# ETHERNET.net
KiCad netlist of a schematic drawn in Altium Designer
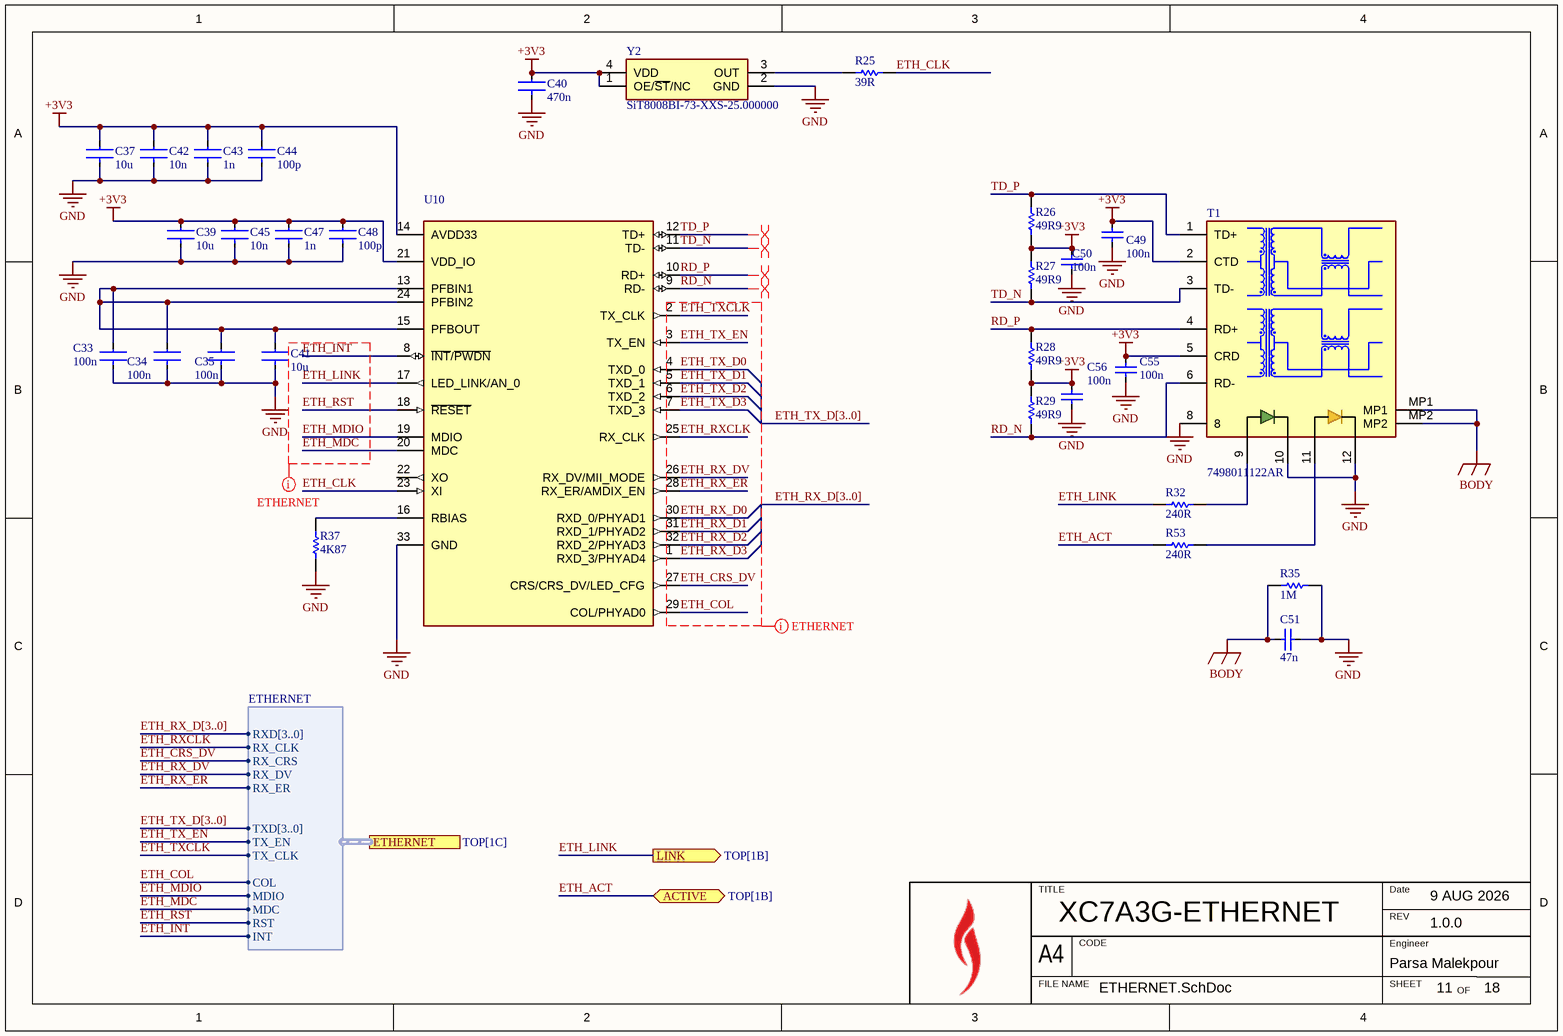
[diagram p0: ETHERNET.SchDoc]

(export (version "E")
  (design (tool "Eeschema 10.0.6"))
  (components
    (comp (ref "C33")
      (value "100n")
      (footprint "FP-C1005-050-0_05-IPC_C")
      (description "Multilayer Ceramic Capacitors 100nF ±10% 50V X7R SMD 0402")
      (fields (field (name "VOLTAGE") "50V") (field (name "TOLERANCE") "10%"))
      (libsource (lib "Schlib1") (part "b4654b650e69147ec39a6b967a45e02"))
    )
    (comp (ref "C34")
      (value "100n")
      (footprint "FP-C1005-050-0_05-IPC_C")
      (description "Multilayer Ceramic Capacitors 100nF ±10% 50V X7R SMD 0402")
      (fields (field (name "VOLTAGE") "50V") (field (name "TOLERANCE") "10%"))
      (libsource (lib "Schlib1") (part "b4654b650e69147ec39a6b967a45e02"))
    )
    (comp (ref "C35")
      (value "100n")
      (footprint "FP-C1005-050-0_05-IPC_C")
      (description "Multilayer Ceramic Capacitors 100nF ±10% 50V X7R SMD 0402")
      (fields (field (name "VOLTAGE") "50V") (field (name "TOLERANCE") "10%"))
      (libsource (lib "Schlib1") (part "b4654b650e69147ec39a6b967a45e02"))
    )
    (comp (ref "C37")
      (value "10u")
      (footprint "FP-C1608-080-0_1-IPC_C")
      (description "Multilayer Ceramic Capacitors 10μF ±10% 6.3V JB SMD 0603")
      (fields (field (name "TOLERANCE") "10%") (field (name "Comment") "C1608JB0J106K080AB"))
      (libsource (lib "Schlib1") (part "236180d848d6139a670b325ea6854c9"))
    )
    (comp (ref "C39")
      (value "10u")
      (footprint "FP-C1608-080-0_1-IPC_C")
      (description "Multilayer Ceramic Capacitors 10μF ±10% 6.3V JB SMD 0603")
      (fields (field (name "TOLERANCE") "10%") (field (name "Comment") "C1608JB0J106K080AB"))
      (libsource (lib "Schlib1") (part "236180d848d6139a670b325ea6854c9"))
    )
    (comp (ref "C40")
      (value "470n")
      (footprint "FP-C1005-050-0_05-IPC_C")
      (description "Multilayer Ceramic Capacitors 470nF ±10% 25V X5R SMD 0402")
      (fields (field (name "VOLTAGE") "25V") (field (name "TOLERANCE") "10%"))
      (libsource (lib "Schlib1") (part "b4654b650e69147ec39a6b967a45e02"))
    )
    (comp (ref "C41")
      (value "10u")
      (footprint "FP-C1608-080-0_1-IPC_C")
      (description "Multilayer Ceramic Capacitors 10μF ±10% 6.3V JB SMD 0603")
      (fields (field (name "TOLERANCE") "10%") (field (name "Comment") "C1608JB0J106K080AB"))
      (libsource (lib "Schlib1") (part "236180d848d6139a670b325ea6854c9"))
    )
    (comp (ref "C42")
      (value "10n")
      (footprint "FP-C1005-050-0_05-IPC_C")
      (description "Multilayer Ceramic Capacitors 10nF ±10% 100V X7S SMD 0402")
      (fields (field (name "TOLERANCE") "10%") (field (name "VOLTAGE") "100V"))
      (libsource (lib "Schlib1") (part "b4654b650e69147ec39a6b967a45e02"))
    )
    (comp (ref "C43")
      (value "1n")
      (footprint "FP-C1005-050-0_05-IPC_C")
      (description "Multilayer Ceramic Capacitors 1nF ±5% 100V C0G SMD 0402")
      (fields (field (name "TOLERANCE") "5%") (field (name "PART NUMBER") "C1005C0G2A102J050BC"))
      (libsource (lib "Schlib1") (part "b4654b650e69147ec39a6b967a45e02"))
    )
    (comp (ref "C44")
      (value "100p")
      (footprint "FP-C1005-050-0_05-IPC_C")
      (description "Multilayer Ceramic Capacitors 100pF ±5% 50V C0G SMD 0402")
      (fields (field (name "TOLERANCE") "5%") (field (name "VOLTAGE") "50V"))
      (libsource (lib "Schlib1") (part "b4654b650e69147ec39a6b967a45e02"))
    )
    (comp (ref "C45")
      (value "10n")
      (footprint "FP-C1005-050-0_05-IPC_C")
      (description "Multilayer Ceramic Capacitors 10nF ±10% 100V X7S SMD 0402")
      (fields (field (name "TOLERANCE") "10%") (field (name "VOLTAGE") "100V"))
      (libsource (lib "Schlib1") (part "b4654b650e69147ec39a6b967a45e02"))
    )
    (comp (ref "C47")
      (value "1n")
      (footprint "FP-C1005-050-0_05-IPC_C")
      (description "Multilayer Ceramic Capacitors 1nF ±5% 100V C0G SMD 0402")
      (fields (field (name "TOLERANCE") "5%") (field (name "PART NUMBER") "C1005C0G2A102J050BC"))
      (libsource (lib "Schlib1") (part "b4654b650e69147ec39a6b967a45e02"))
    )
    (comp (ref "C48")
      (value "100p")
      (footprint "FP-C1005-050-0_05-IPC_C")
      (description "Multilayer Ceramic Capacitors 100pF ±5% 50V C0G SMD 0402")
      (fields (field (name "TOLERANCE") "5%") (field (name "VOLTAGE") "50V"))
      (libsource (lib "Schlib1") (part "b4654b650e69147ec39a6b967a45e02"))
    )
    (comp (ref "C49")
      (value "100n")
      (footprint "FP-C1005-050-0_05-IPC_C")
      (description "MLCC 100nF ±10% 50V X7R SMD 0402")
      (fields (field (name "VOLTAGE") "50V") (field (name "TOLERANCE") "10%"))
      (libsource (lib "Schlib1") (part "C1005X7R1H104K050BB"))
    )
    (comp (ref "C50")
      (value "100n")
      (footprint "FP-C1005-050-0_05-IPC_C")
      (description "MLCC 100nF ±10% 50V X7R SMD 0402")
      (fields (field (name "VOLTAGE") "50V") (field (name "TOLERANCE") "10%"))
      (libsource (lib "Schlib1") (part "C1005X7R1H104K050BB"))
    )
    (comp (ref "C51")
      (value "47n")
      (footprint "pcblib1:FP-C1005-050-0_05-IPC_C")
      (description "MLCC 47nF ±10% 50V X7R SMD 0402")
      (fields (field (name "VOLTAGE") "50V") (field (name "TOLERANCE") "10%"))
      (libsource (lib "Schlib1") (part "C1005X7R1H473K050BB"))
    )
    (comp (ref "C55")
      (value "100n")
      (footprint "FP-C1005-050-0_05-IPC_C")
      (description "MLCC 100nF ±10% 50V X7R SMD 0402")
      (fields (field (name "VOLTAGE") "50V") (field (name "TOLERANCE") "10%"))
      (libsource (lib "Schlib1") (part "C1005X7R1H104K050BB"))
    )
    (comp (ref "C56")
      (value "100n")
      (footprint "FP-C1005-050-0_05-IPC_C")
      (description "MLCC 100nF ±10% 50V X7R SMD 0402")
      (fields (field (name "VOLTAGE") "50V") (field (name "TOLERANCE") "10%"))
      (libsource (lib "Schlib1") (part "C1005X7R1H104K050BB"))
    )
    (comp (ref "R25")
      (value "39R")
      (footprint "RESC1005X40X25LL05T10")
      (fields (field (name "MANUFACTURER") "Yageo / Phycomp") (field (name "PART NUMBER") "RC0402FR-0739RL"))
      (libsource (lib "Schlib1") (part "RC0402FR-0739RL"))
    )
    (comp (ref "R26")
      (value "49R9")
      (footprint "RESC1005X40X25LL05T10")
      (fields (field (name "MANUFACTURER") "Yageo / Phycomp") (field (name "PART NUMBER") "RC0402FR-074R99L"))
      (libsource (lib "Schlib1") (part "RC0402FR-074R99L"))
    )
    (comp (ref "R27")
      (value "49R9")
      (footprint "RESC1005X40X25LL05T10")
      (fields (field (name "MANUFACTURER") "Yageo / Phycomp") (field (name "PART NUMBER") "RC0402FR-074R99L"))
      (libsource (lib "Schlib1") (part "RC0402FR-074R99L"))
    )
    (comp (ref "R28")
      (value "49R9")
      (footprint "RESC1005X40X25LL05T10")
      (fields (field (name "MANUFACTURER") "Yageo / Phycomp") (field (name "PART NUMBER") "RC0402FR-074R99L"))
      (libsource (lib "Schlib1") (part "RC0402FR-074R99L"))
    )
    (comp (ref "R29")
      (value "49R9")
      (footprint "RESC1005X40X25LL05T10")
      (fields (field (name "MANUFACTURER") "Yageo / Phycomp") (field (name "PART NUMBER") "RC0402FR-074R99L"))
      (libsource (lib "Schlib1") (part "RC0402FR-074R99L"))
    )
    (comp (ref "R32")
      (value "240R")
      (footprint "pcblib1:RESC1005X40X25LL05T10")
      (description "240R 0.063W 1% 0402 (1005 Metric)  SMD")
      (fields (field (name "POWER") "0.063 W") (field (name "TOLERANCE") "1 %"))
      (libsource (lib "Schlib1") (part "RC0402FR-07240RL"))
    )
    (comp (ref "R35")
      (value "1M")
      (footprint "RESC1005X40X25LL05T10")
      (fields (field (name "MANUFACTURER") "Yageo / Phycomp") (field (name "PART NUMBER") "RC0402FR-071ML"))
      (libsource (lib "Schlib1") (part "RC0402FR-071ML"))
    )
    (comp (ref "R37")
      (value "4K87")
      (footprint "RESC1005X40X25LL05T10")
      (fields (field (name "PART NUMBER") "RC0402FR-074K87L") (field (name "MANUFACTURER") "Yageo / Phycomp"))
      (libsource (lib "Schlib1") (part "RC0402FR-074K87L"))
    )
    (comp (ref "R53")
      (value "240R")
      (footprint "pcblib1:RESC1005X40X25LL05T10")
      (description "240R 0.063W 1% 0402 (1005 Metric)  SMD")
      (fields (field (name "POWER") "0.063 W") (field (name "TOLERANCE") "1 %"))
      (libsource (lib "Schlib1") (part "RC0402FR-07240RL"))
    )
    (comp (ref "T1")
      (value "7498011122AR")
      (footprint "PcbLib1:7498011122AR")
      (description "Transformer")
      (fields (field (name "MOUSER PART NUMBER") "710-7498011122AR"))
      (libsource (lib "Schlib1") (part "7498011122AR"))
    )
    (comp (ref "U10")
      (value "~")
      (footprint "QFN50P500X500X100-33N-D")
      (description "Integrated Circuit")
      (fields
        (field (name "MANUFACTURER_PART_NUMBER") "TLK106RHBR")
        (field (name "MOUSER PART NUMBER") "595-TLK106RHBR")
      )
      (libsource (lib "Schlib1") (part "TLK106RHBR"))
    )
    (comp (ref "Y2")
      (value "SiT8008BI-73-XXS-25.000000")
      (footprint "QFN_2016_4pins")
      (description "Crystal or Oscillator")
      (libsource (lib "Schlib1") (part "SiT8008BI-73-XXS-25.000000"))
    )
  )
  (nets
    (net (code "2") (name "+3V3") (class "Default")
      (node (ref "C37") (pin "1") (pinfunction "1_1") (pintype "passive"))
      (node (ref "C39") (pin "1") (pinfunction "1_1") (pintype "passive"))
      (node (ref "C40") (pin "2") (pinfunction "2_2") (pintype "passive"))
      (node (ref "C42") (pin "2") (pinfunction "2_2") (pintype "passive"))
      (node (ref "C43") (pin "2") (pinfunction "2_2") (pintype "passive"))
      (node (ref "C44") (pin "2") (pinfunction "2_2") (pintype "passive"))
      (node (ref "C45") (pin "2") (pinfunction "2_2") (pintype "passive"))
      (node (ref "C47") (pin "2") (pinfunction "2_2") (pintype "passive"))
      (node (ref "C48") (pin "2") (pinfunction "2_2") (pintype "passive"))
      (node (ref "C49") (pin "2") (pinfunction "2_2") (pintype "passive"))
      (node (ref "C50") (pin "2") (pinfunction "2_2") (pintype "passive"))
      (node (ref "C55") (pin "2") (pinfunction "2_2") (pintype "passive"))
      (node (ref "C56") (pin "2") (pinfunction "2_2") (pintype "passive"))
      (node (ref "R26") (pin "1") (pinfunction "1_1") (pintype "passive"))
      (node (ref "R27") (pin "2") (pinfunction "2_2") (pintype "passive"))
      (node (ref "R28") (pin "1") (pinfunction "1_1") (pintype "passive"))
      (node (ref "R29") (pin "2") (pinfunction "2_2") (pintype "passive"))
      (node (ref "T1") (pin "2") (pinfunction "CTD_2") (pintype "passive"))
      (node (ref "T1") (pin "5") (pinfunction "CRD_5") (pintype "passive"))
      (node (ref "U10") (pin "14") (pinfunction "AVDD33_14") (pintype "power_in"))
      (node (ref "U10") (pin "21") (pinfunction "VDD_IO_21") (pintype "power_in"))
      (node (ref "Y2") (pin "1") (pinfunction "OE/~{ST}/NC_1") (pintype "passive"))
      (node (ref "Y2") (pin "4") (pinfunction "VDD_4") (pintype "passive"))
    )
    (net (code "4") (name "/ETH_ACT") (class "Default")
      (node (ref "R53") (pin "1") (pinfunction "1_1") (pintype "passive"))
    )
    (net (code "5") (name "/ETH_CLK") (class "Default")
      (node (ref "R25") (pin "2") (pinfunction "2_2") (pintype "passive"))
      (node (ref "U10") (pin "23") (pinfunction "XI_23") (pintype "input"))
    )
    (net (code "6") (name "/ETH_COL") (class "Default")
      (node (ref "U10") (pin "29") (pinfunction "COL/PHYAD0_29") (pintype "output"))
    )
    (net (code "7") (name "/ETH_CRS_DV") (class "Default")
      (node (ref "U10") (pin "27") (pinfunction "CRS/CRS_DV/LED_CFG_27") (pintype "output"))
    )
    (net (code "8") (name "/ETH_INT") (class "Default")
      (node (ref "U10") (pin "8") (pinfunction "~{INT}/~{PWDN}_8") (pintype "bidirectional"))
    )
    (net (code "9") (name "/ETH_LINK") (class "Default")
      (node (ref "R32") (pin "1") (pinfunction "1_1") (pintype "passive"))
      (node (ref "U10") (pin "17") (pinfunction "LED_LINK/AN_0_17") (pintype "output"))
    )
    (net (code "10") (name "/ETH_MDC") (class "Default")
      (node (ref "U10") (pin "20") (pinfunction "MDC_20") (pintype "passive"))
    )
    (net (code "11") (name "/ETH_MDIO") (class "Default")
      (node (ref "U10") (pin "19") (pinfunction "MDIO_19") (pintype "passive"))
    )
    (net (code "12") (name "/ETH_RST") (class "Default")
      (node (ref "U10") (pin "18") (pinfunction "~{RESET}_18") (pintype "input"))
    )
    (net (code "13") (name "/ETH_RXCLK") (class "Default")
      (node (ref "U10") (pin "25") (pinfunction "RX_CLK_25") (pintype "output"))
    )
    (net (code "14") (name "/ETH_RX_D0") (class "Default")
      (node (ref "U10") (pin "30") (pinfunction "RXD_0/PHYAD1_30") (pintype "output"))
    )
    (net (code "15") (name "/ETH_RX_D1") (class "Default")
      (node (ref "U10") (pin "31") (pinfunction "RXD_1/PHYAD2_31") (pintype "output"))
    )
    (net (code "16") (name "/ETH_RX_D2") (class "Default")
      (node (ref "U10") (pin "32") (pinfunction "RXD_2/PHYAD3_32") (pintype "output"))
    )
    (net (code "17") (name "/ETH_RX_D3") (class "Default")
      (node (ref "U10") (pin "1") (pinfunction "RXD_3/PHYAD4_1") (pintype "output"))
    )
    (net (code "18") (name "/ETH_RX_DV") (class "Default")
      (node (ref "U10") (pin "26") (pinfunction "RX_DV/MII_MODE_26") (pintype "output"))
    )
    (net (code "20") (name "/ETH_RX_ER") (class "Default")
      (node (ref "U10") (pin "28") (pinfunction "RX_ER/AMDIX_EN_28") (pintype "output"))
    )
    (net (code "21") (name "/ETH_TXCLK") (class "Default")
      (node (ref "U10") (pin "2") (pinfunction "TX_CLK_2") (pintype "output"))
    )
    (net (code "22") (name "/ETH_TX_D0") (class "Default")
      (node (ref "U10") (pin "4") (pinfunction "TXD_0_4") (pintype "input"))
    )
    (net (code "23") (name "/ETH_TX_D1") (class "Default")
      (node (ref "U10") (pin "5") (pinfunction "TXD_1_5") (pintype "input"))
    )
    (net (code "24") (name "/ETH_TX_D2") (class "Default")
      (node (ref "U10") (pin "6") (pinfunction "TXD_2_6") (pintype "input"))
    )
    (net (code "25") (name "/ETH_TX_D3") (class "Default")
      (node (ref "U10") (pin "7") (pinfunction "TXD_3_7") (pintype "input"))
    )
    (net (code "27") (name "/ETH_TX_EN") (class "Default")
      (node (ref "U10") (pin "3") (pinfunction "TX_EN_3") (pintype "input"))
    )
    (net (code "28") (name "/RD_N") (class "Default")
      (node (ref "R29") (pin "1") (pinfunction "1_1") (pintype "passive"))
      (node (ref "T1") (pin "6") (pinfunction "RD-_6") (pintype "passive"))
      (node (ref "U10") (pin "9") (pinfunction "RD-_9") (pintype "bidirectional"))
    )
    (net (code "29") (name "/RD_P") (class "Default")
      (node (ref "R28") (pin "2") (pinfunction "2_2") (pintype "passive"))
      (node (ref "T1") (pin "4") (pinfunction "RD+_4") (pintype "passive"))
      (node (ref "U10") (pin "10") (pinfunction "RD+_10") (pintype "bidirectional"))
    )
    (net (code "30") (name "/TD_N") (class "Default")
      (node (ref "R27") (pin "1") (pinfunction "1_1") (pintype "passive"))
      (node (ref "T1") (pin "3") (pinfunction "TD-_3") (pintype "passive"))
      (node (ref "U10") (pin "11") (pinfunction "TD-_11") (pintype "bidirectional"))
    )
    (net (code "31") (name "/TD_P") (class "Default")
      (node (ref "R26") (pin "2") (pinfunction "2_2") (pintype "passive"))
      (node (ref "T1") (pin "1") (pinfunction "TD+_1") (pintype "passive"))
      (node (ref "U10") (pin "12") (pinfunction "TD+_12") (pintype "bidirectional"))
    )
    (net (code "33") (name "BODY") (class "Default")
      (node (ref "C51") (pin "1") (pinfunction "1_1") (pintype "passive"))
      (node (ref "R35") (pin "1") (pinfunction "1_1") (pintype "passive"))
      (node (ref "T1") (pin "MP1") (pinfunction "MP1_MP1") (pintype "passive"))
      (node (ref "T1") (pin "MP2") (pinfunction "MP2_MP2") (pintype "passive"))
    )
    (net (code "34") (name "GND") (class "Default")
      (node (ref "C33") (pin "1") (pinfunction "1_1") (pintype "passive"))
      (node (ref "C34") (pin "1") (pinfunction "1_1") (pintype "passive"))
      (node (ref "C35") (pin "1") (pinfunction "1_1") (pintype "passive"))
      (node (ref "C37") (pin "2") (pinfunction "2_2") (pintype "passive"))
      (node (ref "C39") (pin "2") (pinfunction "2_2") (pintype "passive"))
      (node (ref "C40") (pin "1") (pinfunction "1_1") (pintype "passive"))
      (node (ref "C41") (pin "2") (pinfunction "2_2") (pintype "passive"))
      (node (ref "C42") (pin "1") (pinfunction "1_1") (pintype "passive"))
      (node (ref "C43") (pin "1") (pinfunction "1_1") (pintype "passive"))
      (node (ref "C44") (pin "1") (pinfunction "1_1") (pintype "passive"))
      (node (ref "C45") (pin "1") (pinfunction "1_1") (pintype "passive"))
      (node (ref "C47") (pin "1") (pinfunction "1_1") (pintype "passive"))
      (node (ref "C48") (pin "1") (pinfunction "1_1") (pintype "passive"))
      (node (ref "C49") (pin "1") (pinfunction "1_1") (pintype "passive"))
      (node (ref "C50") (pin "1") (pinfunction "1_1") (pintype "passive"))
      (node (ref "C51") (pin "2") (pinfunction "2_2") (pintype "passive"))
      (node (ref "C55") (pin "1") (pinfunction "1_1") (pintype "passive"))
      (node (ref "C56") (pin "1") (pinfunction "1_1") (pintype "passive"))
      (node (ref "R35") (pin "2") (pinfunction "2_2") (pintype "passive"))
      (node (ref "R37") (pin "1") (pinfunction "1_1") (pintype "passive"))
      (node (ref "T1") (pin "10") (pinfunction "K_YELLOW_10") (pintype "passive"))
      (node (ref "T1") (pin "12") (pinfunction "K_GREEN_12") (pintype "passive"))
      (node (ref "T1") (pin "8") (pinfunction "8_8") (pintype "passive"))
      (node (ref "U10") (pin "33") (pinfunction "GND_33") (pintype "passive"))
      (node (ref "Y2") (pin "2") (pinfunction "GND_2") (pintype "passive"))
    )
    (net (code "35") (name "Net-(T1-A_GREEN)") (class "Default")
      (node (ref "R53") (pin "2") (pinfunction "2_2") (pintype "passive"))
      (node (ref "T1") (pin "11") (pinfunction "A_GREEN_11") (pintype "passive"))
    )
    (net (code "36") (name "Net-(T1-A_YELLOW)") (class "Default")
      (node (ref "R32") (pin "2") (pinfunction "2_2") (pintype "passive"))
      (node (ref "T1") (pin "9") (pinfunction "A_YELLOW_9") (pintype "passive"))
    )
    (net (code "37") (name "Net-(U10-PFBIN1)") (class "Default")
      (node (ref "C33") (pin "2") (pinfunction "2_2") (pintype "passive"))
      (node (ref "C34") (pin "2") (pinfunction "2_2") (pintype "passive"))
      (node (ref "C35") (pin "2") (pinfunction "2_2") (pintype "passive"))
      (node (ref "C41") (pin "1") (pinfunction "1_1") (pintype "passive"))
      (node (ref "U10") (pin "13") (pinfunction "PFBIN1_13") (pintype "power_in"))
      (node (ref "U10") (pin "15") (pinfunction "PFBOUT_15") (pintype "power_in"))
      (node (ref "U10") (pin "24") (pinfunction "PFBIN2_24") (pintype "power_in"))
    )
    (net (code "38") (name "Net-(U10-RBIAS)") (class "Default")
      (node (ref "R37") (pin "2") (pinfunction "2_2") (pintype "passive"))
      (node (ref "U10") (pin "16") (pinfunction "RBIAS_16") (pintype "passive"))
    )
    (net (code "39") (name "Net-(Y2-OUT)") (class "Default")
      (node (ref "R25") (pin "1") (pinfunction "1_1") (pintype "passive"))
      (node (ref "Y2") (pin "3") (pinfunction "OUT_3") (pintype "passive"))
    )
    (net (code "40") (name "unconnected-(U10-XO-Pad22)") (class "Default")
      (node (ref "U10") (pin "22") (pinfunction "XO_22") (pintype "output"))
    )
  )
)
